# test_add_res.net
KiCad netlist of a schematic drawn in EAGLE
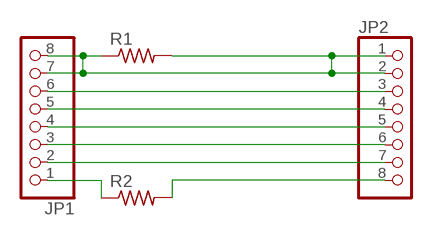
[diagram p0: schematic, sheet 1]

(export (version "E")
  (design (tool "Eeschema 10.0.6"))
  (components
    (comp (ref "JP1")
      (value "PINHD-1X8")
      (footprint "eagle-import:1X08")
      (libsource (lib "eagle-import") (part "PINHD-1X8"))
    )
    (comp (ref "JP2")
      (value "PINHD-1X8")
      (footprint "eagle-import:1X08")
      (libsource (lib "eagle-import") (part "PINHD-1X8"))
    )
    (comp (ref "R1")
      (value "R-US_R0805")
      (footprint "eagle-import:R0805")
      (libsource (lib "eagle-import") (part "R-US_R0805"))
    )
    (comp (ref "R2")
      (value "R-US_R0805")
      (footprint "eagle-import:R0805")
      (libsource (lib "eagle-import") (part "R-US_R0805"))
    )
  )
  (nets
    (net (code "1") (name "Net-(JP1-Pad1)") (class "Default")
      (node (ref "JP1") (pin "1") (pinfunction "1_1") (pintype "passive"))
      (node (ref "R2") (pin "1") (pinfunction "1_1") (pintype "passive"))
    )
    (net (code "2") (name "Net-(JP1-Pad2)") (class "Default")
      (node (ref "JP1") (pin "2") (pinfunction "2_2") (pintype "passive"))
      (node (ref "JP2") (pin "7") (pinfunction "7_7") (pintype "passive"))
    )
    (net (code "3") (name "Net-(JP1-Pad3)") (class "Default")
      (node (ref "JP1") (pin "3") (pinfunction "3_3") (pintype "passive"))
      (node (ref "JP2") (pin "6") (pinfunction "6_6") (pintype "passive"))
    )
    (net (code "4") (name "Net-(JP1-Pad4)") (class "Default")
      (node (ref "JP1") (pin "4") (pinfunction "4_4") (pintype "passive"))
      (node (ref "JP2") (pin "5") (pinfunction "5_5") (pintype "passive"))
    )
    (net (code "5") (name "Net-(JP1-Pad5)") (class "Default")
      (node (ref "JP1") (pin "5") (pinfunction "5_5") (pintype "passive"))
      (node (ref "JP2") (pin "4") (pinfunction "4_4") (pintype "passive"))
    )
    (net (code "6") (name "Net-(JP1-Pad6)") (class "Default")
      (node (ref "JP1") (pin "6") (pinfunction "6_6") (pintype "passive"))
      (node (ref "JP2") (pin "3") (pinfunction "3_3") (pintype "passive"))
    )
    (net (code "7") (name "Net-(JP1-Pad7)") (class "Default")
      (node (ref "JP1") (pin "7") (pinfunction "7_7") (pintype "passive"))
      (node (ref "JP1") (pin "8") (pinfunction "8_8") (pintype "passive"))
      (node (ref "JP2") (pin "1") (pinfunction "1_1") (pintype "passive"))
      (node (ref "JP2") (pin "2") (pinfunction "2_2") (pintype "passive"))
      (node (ref "R1") (pin "1") (pinfunction "1_1") (pintype "passive"))
      (node (ref "R1") (pin "2") (pinfunction "2_2") (pintype "passive"))
    )
    (net (code "8") (name "Net-(JP2-Pad8)") (class "Default")
      (node (ref "JP2") (pin "8") (pinfunction "8_8") (pintype "passive"))
      (node (ref "R2") (pin "2") (pinfunction "2_2") (pintype "passive"))
    )
  )
)
